# photodiode.net
KiCad netlist of a schematic drawn in EAGLE
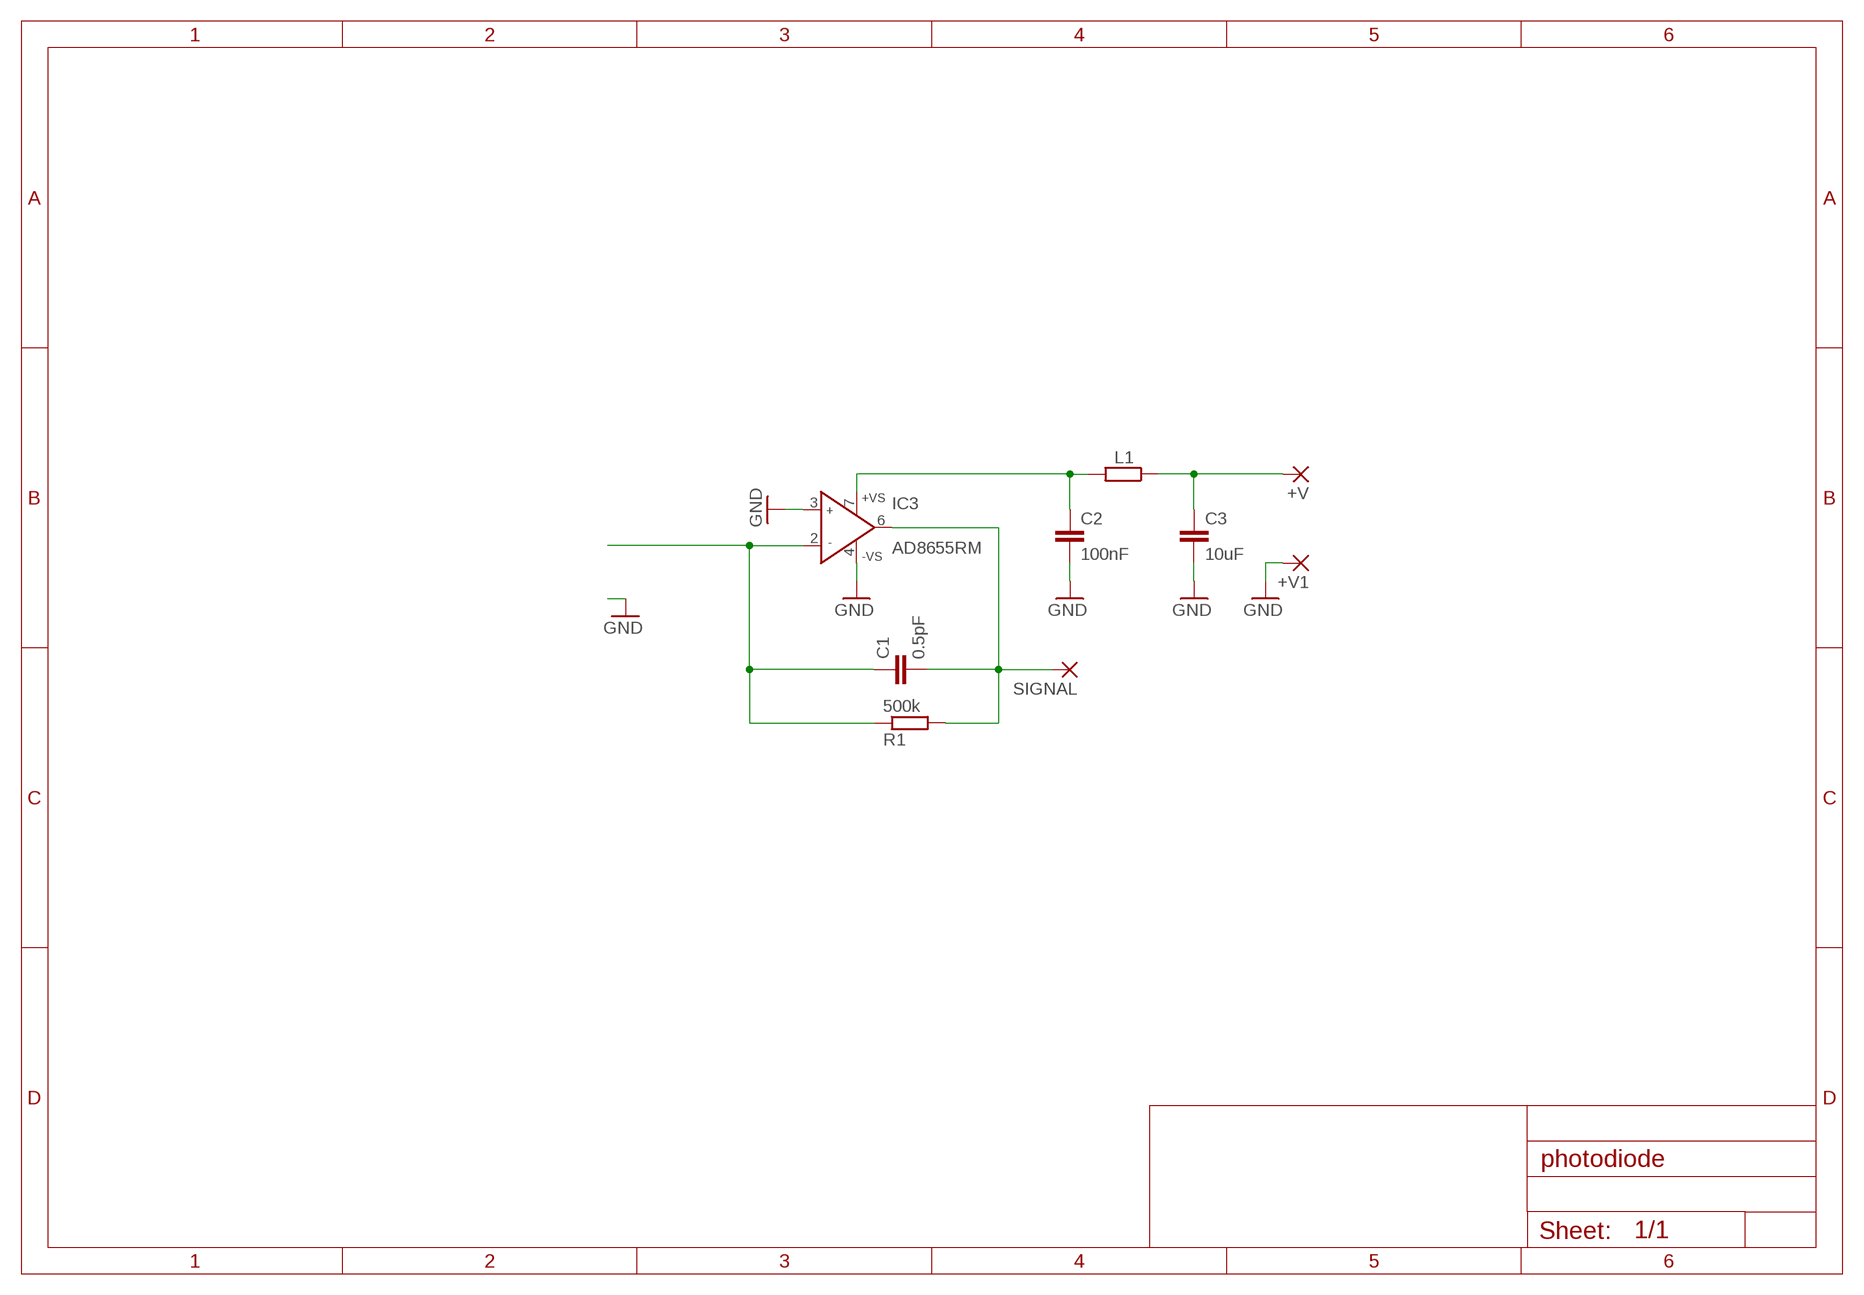
[diagram p0: schematic, sheet 1]

(export (version "E")
  (design (tool "Eeschema 10.0.6"))
  (components
    (comp (ref "+V")
      (value "WIREPADSMD1,27-254")
      (footprint "eagle-import:SMD1,27-2,54")
      (libsource (lib "eagle-import") (part "WIREPADSMD1,27-254"))
    )
    (comp (ref "+V1")
      (value "WIREPADSMD1,27-254")
      (footprint "eagle-import:SMD1,27-2,54")
      (libsource (lib "eagle-import") (part "WIREPADSMD1,27-254"))
    )
    (comp (ref "C1")
      (value "0.5pF")
      (footprint "eagle-import:C0402")
      (libsource (lib "eagle-import") (part "C-EUC0402"))
    )
    (comp (ref "C2")
      (value "100nF")
      (footprint "eagle-import:C0402")
      (libsource (lib "eagle-import") (part "C-EUC0402"))
    )
    (comp (ref "C3")
      (value "10uF")
      (footprint "eagle-import:C0603")
      (libsource (lib "eagle-import") (part "C-EUC0603"))
    )
    (comp (ref "IC3")
      (value "AD8655RM")
      (footprint "eagle-import:MSOP08")
      (fields (field (name "MF") "ALTERA CORPORATION") (field (name "MPN") "AD8655ARZ"))
      (libsource (lib "eagle-import") (part "AD8655RM"))
    )
    (comp (ref "L1")
      (value "1k@100M")
      (footprint "eagle-import:R0402")
      (libsource (lib "eagle-import") (part "R-EU_R0402"))
    )
    (comp (ref "R1")
      (value "500k")
      (footprint "eagle-import:R0402")
      (libsource (lib "eagle-import") (part "R-EU_R0402"))
    )
    (comp (ref "SIGNAL")
      (value "WIREPADSMD1,27-254")
      (footprint "eagle-import:SMD1,27-2,54")
      (libsource (lib "eagle-import") (part "WIREPADSMD1,27-254"))
    )
  )
  (nets
    (net (code "1") (name "GND") (class "Default")
      (node (ref "+V1") (pin "1") (pinfunction "P_1") (pintype "passive"))
      (node (ref "C2") (pin "2") (pinfunction "2_2") (pintype "passive"))
      (node (ref "C3") (pin "2") (pinfunction "2_2") (pintype "passive"))
      (node (ref "IC3") (pin "3") (pinfunction "IN+_3") (pintype "input"))
      (node (ref "IC3") (pin "4") (pinfunction "-VS_4") (pintype "input"))
    )
    (net (code "2") (name "Net-(+V-P)") (class "Default")
      (node (ref "+V") (pin "1") (pinfunction "P_1") (pintype "passive"))
      (node (ref "C3") (pin "1") (pinfunction "1_1") (pintype "passive"))
      (node (ref "L1") (pin "1") (pinfunction "1_1") (pintype "passive"))
    )
    (net (code "3") (name "Net-(IC3-+VS)") (class "Default")
      (node (ref "C2") (pin "1") (pinfunction "1_1") (pintype "passive"))
      (node (ref "IC3") (pin "7") (pinfunction "+VS_7") (pintype "input"))
      (node (ref "L1") (pin "2") (pinfunction "2_2") (pintype "passive"))
    )
    (net (code "4") (name "Net-(IC3-IN-)") (class "Default")
      (node (ref "C1") (pin "1") (pinfunction "1_1") (pintype "passive"))
      (node (ref "IC3") (pin "2") (pinfunction "IN-_2") (pintype "input"))
      (node (ref "R1") (pin "1") (pinfunction "1_1") (pintype "passive"))
    )
    (net (code "5") (name "Net-(IC3-OUT)") (class "Default")
      (node (ref "C1") (pin "2") (pinfunction "2_2") (pintype "passive"))
      (node (ref "IC3") (pin "6") (pinfunction "OUT_6") (pintype "output"))
      (node (ref "R1") (pin "2") (pinfunction "2_2") (pintype "passive"))
      (node (ref "SIGNAL") (pin "1") (pinfunction "P_1") (pintype "passive"))
    )
  )
)
